# Wind_enc_INSP.net
KiCad netlist of a schematic drawn in EAGLE
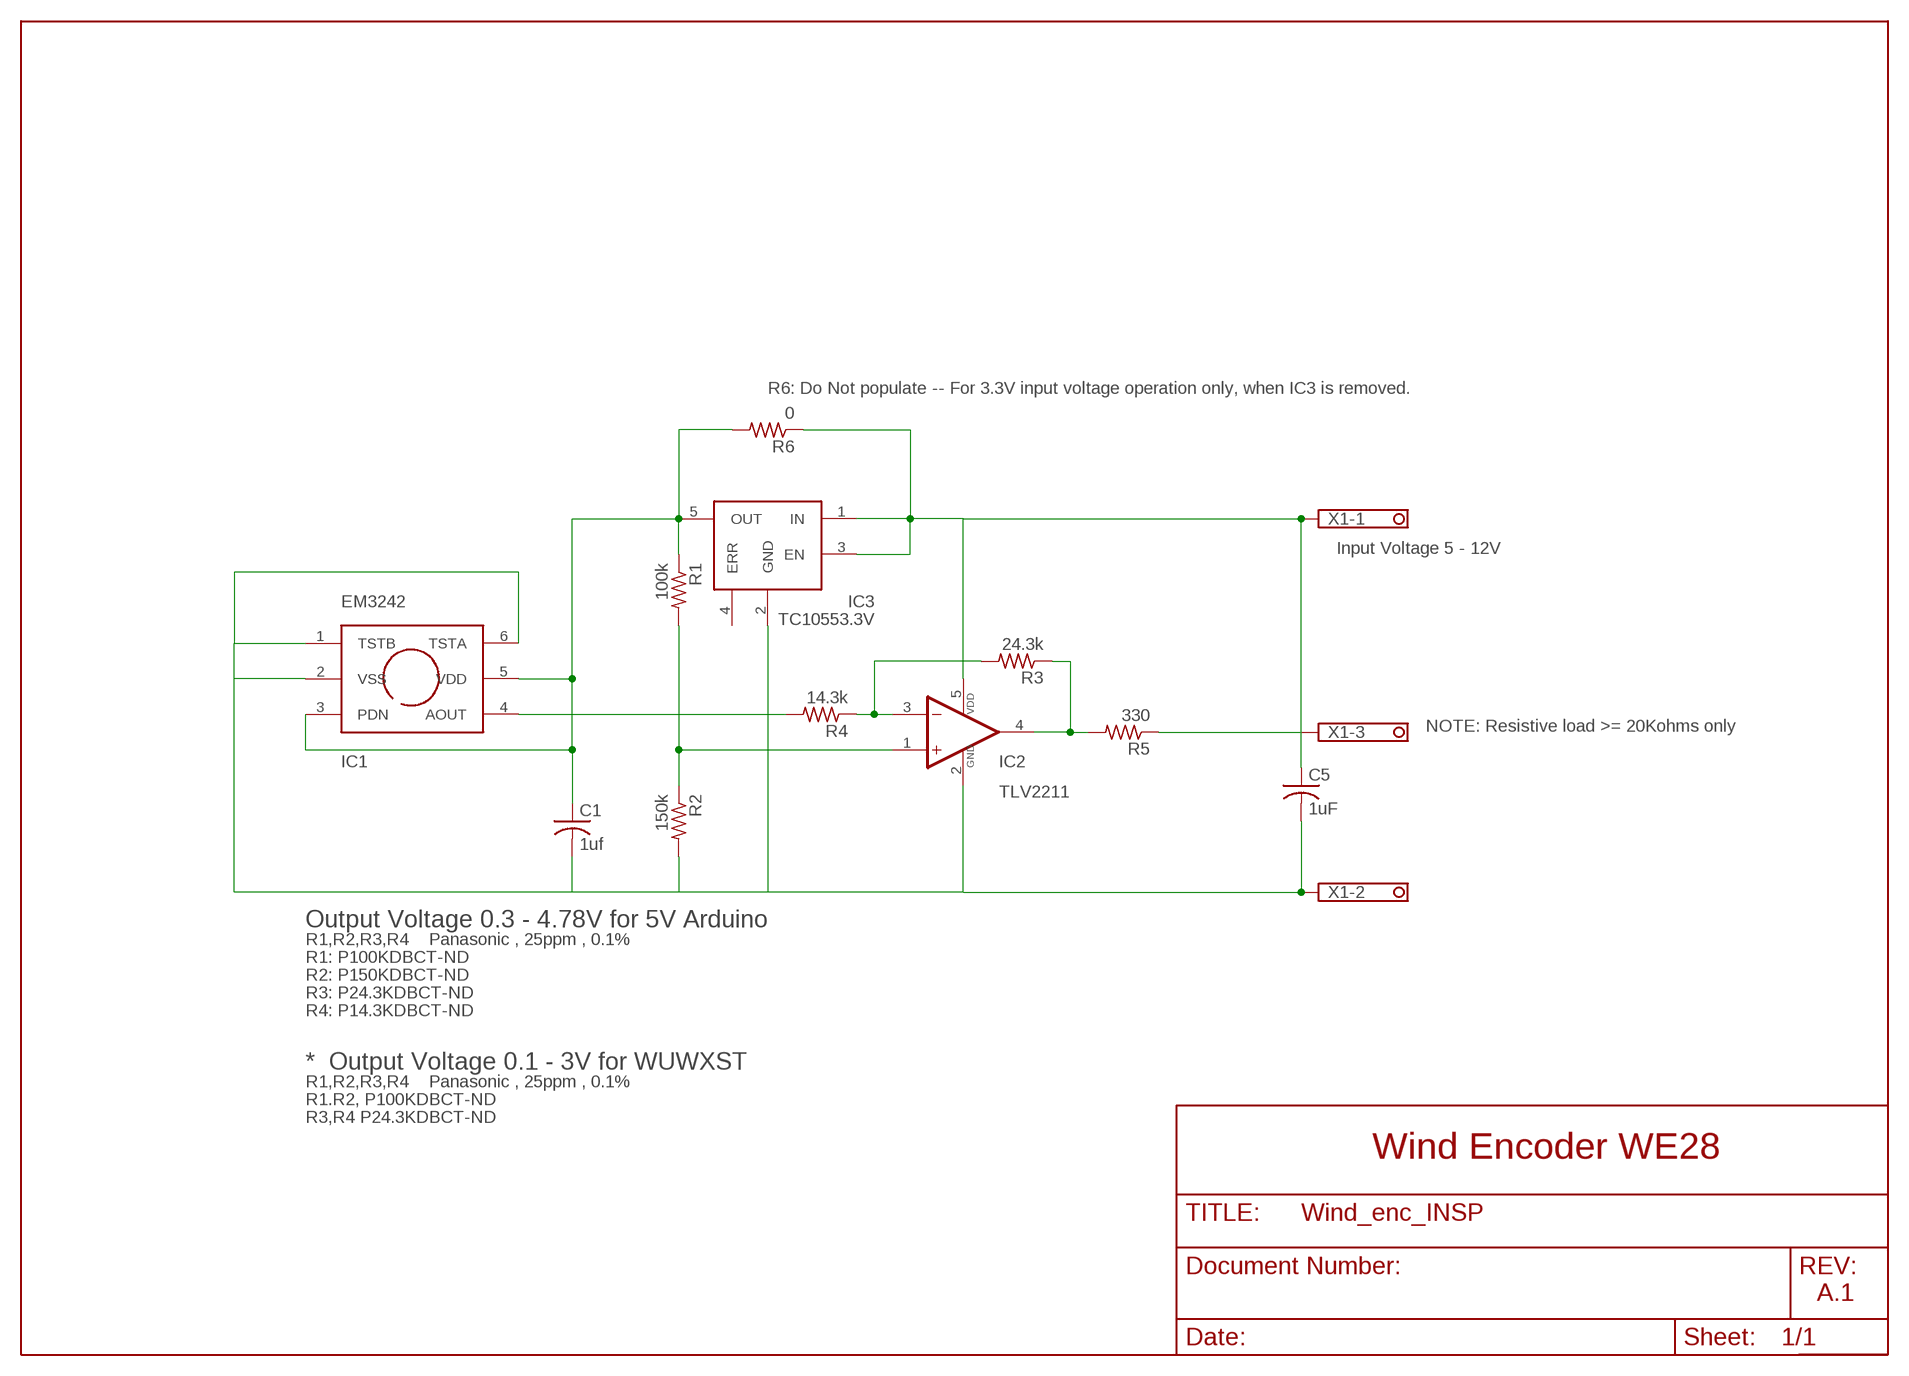
[diagram p0: schematic, sheet 1]

(export (version "E")
  (design (tool "Eeschema 10.0.6"))
  (components
    (comp (ref "C1")
      (value "1uf")
      (footprint "eagle-import:C0805K")
      (libsource (lib "eagle-import") (part "C-USC0805K"))
    )
    (comp (ref "C5")
      (value "1uF")
      (footprint "eagle-import:C0805K")
      (libsource (lib "eagle-import") (part "C-USC0805K"))
    )
    (comp (ref "IC1")
      (value "EM3242")
      (footprint "eagle-import:EM3242_SPECIAL")
      (libsource (lib "eagle-import") (part "EM3242"))
    )
    (comp (ref "IC2")
      (value "TLV2211")
      (footprint "eagle-import:SOT23-5")
      (libsource (lib "eagle-import") (part "TLVB2211"))
    )
    (comp (ref "IC3")
      (value "TC10553.3V")
      (footprint "eagle-import:SOT23-5")
      (libsource (lib "eagle-import") (part "TC10553.3V"))
    )
    (comp (ref "R1")
      (value "100k")
      (footprint "eagle-import:R0603")
      (libsource (lib "eagle-import") (part "R-US_R0603"))
    )
    (comp (ref "R2")
      (value "150k")
      (footprint "eagle-import:R0603")
      (libsource (lib "eagle-import") (part "R-US_R0603"))
    )
    (comp (ref "R3")
      (value "24.3k")
      (footprint "eagle-import:R0603")
      (libsource (lib "eagle-import") (part "R-US_R0603"))
    )
    (comp (ref "R4")
      (value "14.3k")
      (footprint "eagle-import:R0603")
      (libsource (lib "eagle-import") (part "R-US_R0603"))
    )
    (comp (ref "R5")
      (value "330")
      (footprint "eagle-import:R0603")
      (libsource (lib "eagle-import") (part "R-US_R0603"))
    )
    (comp (ref "R6")
      (value "0")
      (footprint "eagle-import:R0603")
      (libsource (lib "eagle-import") (part "R-US_R0603"))
    )
    (comp (ref "X1")
      (value "1751251")
      (footprint "eagle-import:1751251")
      (libsource (lib "eagle-import") (part "1751251"))
    )
  )
  (nets
    (net (code "1") (name "Net-(IC1-AOUT)") (class "Default")
      (node (ref "IC1") (pin "4") (pinfunction "AOUT_4") (pintype "bidirectional"))
      (node (ref "R4") (pin "2") (pinfunction "2_2") (pintype "passive"))
    )
    (net (code "2") (name "Net-(IC1-PDN)") (class "Default")
      (node (ref "C1") (pin "1") (pinfunction "1_1") (pintype "passive"))
      (node (ref "IC1") (pin "3") (pinfunction "PDN_3") (pintype "bidirectional"))
      (node (ref "IC1") (pin "5") (pinfunction "VDD_5") (pintype "bidirectional"))
      (node (ref "IC3") (pin "5") (pinfunction "OUT_5") (pintype "power_in"))
      (node (ref "R1") (pin "1") (pinfunction "1_1") (pintype "passive"))
      (node (ref "R6") (pin "2") (pinfunction "2_2") (pintype "passive"))
    )
    (net (code "3") (name "Net-(IC1-TSTA)") (class "Default")
      (node (ref "C1") (pin "2") (pinfunction "2_2") (pintype "passive"))
      (node (ref "C5") (pin "2") (pinfunction "2_2") (pintype "passive"))
      (node (ref "IC1") (pin "1") (pinfunction "TSTB_1") (pintype "bidirectional"))
      (node (ref "IC1") (pin "2") (pinfunction "VSS_2") (pintype "bidirectional"))
      (node (ref "IC1") (pin "6") (pinfunction "TSTA_6") (pintype "bidirectional"))
      (node (ref "IC2") (pin "2") (pinfunction "VDD_GND_2") (pintype "power_in"))
      (node (ref "IC3") (pin "2") (pinfunction "GND_2") (pintype "power_in"))
      (node (ref "R2") (pin "2") (pinfunction "2_2") (pintype "passive"))
      (node (ref "X1") (pin "2") (pinfunction "K_2") (pintype "passive"))
    )
    (net (code "4") (name "Net-(IC2A-+IN)") (class "Default")
      (node (ref "IC2") (pin "1") (pinfunction "+IN_1") (pintype "input"))
      (node (ref "R1") (pin "2") (pinfunction "2_2") (pintype "passive"))
      (node (ref "R2") (pin "1") (pinfunction "1_1") (pintype "passive"))
    )
    (net (code "5") (name "Net-(IC2A--IN)") (class "Default")
      (node (ref "IC2") (pin "3") (pinfunction "-IN_3") (pintype "input"))
      (node (ref "R3") (pin "2") (pinfunction "2_2") (pintype "passive"))
      (node (ref "R4") (pin "1") (pinfunction "1_1") (pintype "passive"))
    )
    (net (code "6") (name "Net-(IC2A-OUT)") (class "Default")
      (node (ref "IC2") (pin "4") (pinfunction "OUT_4") (pintype "output"))
      (node (ref "R3") (pin "1") (pinfunction "1_1") (pintype "passive"))
      (node (ref "R5") (pin "2") (pinfunction "2_2") (pintype "passive"))
    )
    (net (code "7") (name "Net-(IC2B-VDD)") (class "Default")
      (node (ref "C5") (pin "1") (pinfunction "1_1") (pintype "passive"))
      (node (ref "IC2") (pin "5") (pinfunction "VDD_5") (pintype "power_in"))
      (node (ref "IC3") (pin "1") (pinfunction "IN_1") (pintype "power_in"))
      (node (ref "IC3") (pin "3") (pinfunction "EN_3") (pintype "input"))
      (node (ref "R6") (pin "1") (pinfunction "1_1") (pintype "passive"))
      (node (ref "X1") (pin "1") (pinfunction "K_1") (pintype "passive"))
    )
    (net (code "8") (name "Net-(X1C-K)") (class "Default")
      (node (ref "R5") (pin "1") (pinfunction "1_1") (pintype "passive"))
      (node (ref "X1") (pin "3") (pinfunction "K_3") (pintype "passive"))
    )
    (net (code "9") (name "unconnected-(IC3-ERR-Pad4)") (class "Default")
      (node (ref "IC3") (pin "4") (pinfunction "ERR_4") (pintype "output"))
    )
  )
)
